# Roboteq_Board_V1_0.net
KiCad netlist of a schematic drawn in EAGLE
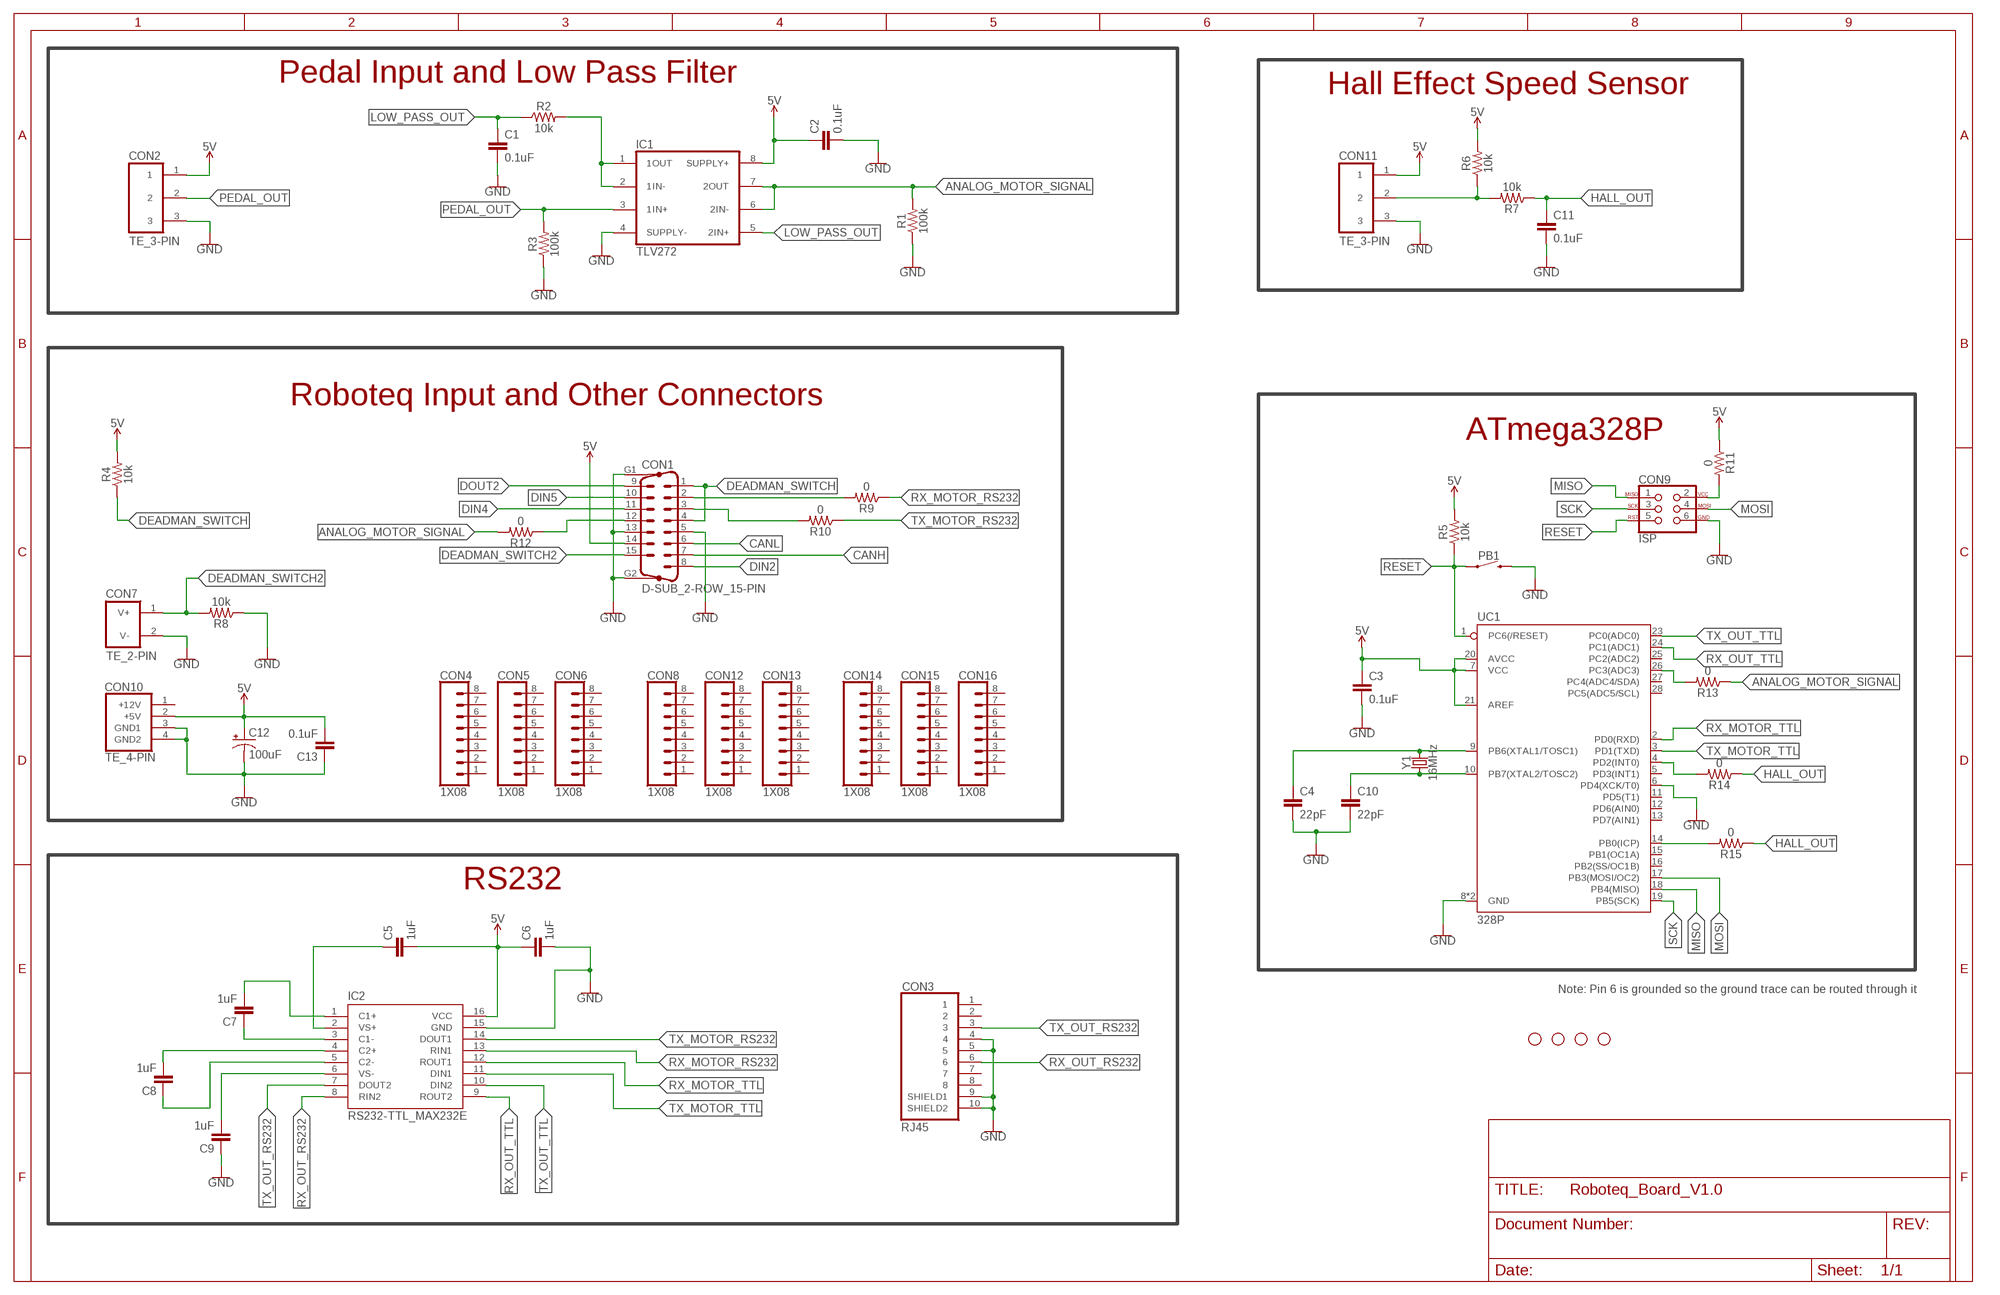
[diagram p0: schematic, sheet 1]

(export (version "E")
  (design (tool "Eeschema 10.0.6"))
  (components
    (comp (ref "C1")
      (value "0.1uF")
      (footprint "eagle-import:CAP-PTH-5MM")
      (libsource (lib "eagle-import") (part "CAPACITOR_CERAMIC_THROUGH-HOLE"))
    )
    (comp (ref "C2")
      (value "0.1uF")
      (footprint "eagle-import:CAP-PTH-5MM")
      (libsource (lib "eagle-import") (part "CAPACITOR_CERAMIC_THROUGH-HOLE"))
    )
    (comp (ref "C3")
      (value "0.1uF")
      (footprint "eagle-import:CAP-PTH-5MM")
      (libsource (lib "eagle-import") (part "CAPACITOR_CERAMIC_THROUGH-HOLE"))
    )
    (comp (ref "C4")
      (value "22pF")
      (footprint "eagle-import:CAP-PTH-5MM")
      (libsource (lib "eagle-import") (part "CAPACITOR_CERAMIC_THROUGH-HOLE"))
    )
    (comp (ref "C5")
      (value "1uF")
      (footprint "eagle-import:CAP-PTH-5MM")
      (libsource (lib "eagle-import") (part "CAPACITOR_CERAMIC_THROUGH-HOLE"))
    )
    (comp (ref "C6")
      (value "1uF")
      (footprint "eagle-import:CAP-PTH-5MM")
      (libsource (lib "eagle-import") (part "CAPACITOR_CERAMIC_THROUGH-HOLE"))
    )
    (comp (ref "C7")
      (value "1uF")
      (footprint "eagle-import:CAP-PTH-5MM")
      (libsource (lib "eagle-import") (part "CAPACITOR_CERAMIC_THROUGH-HOLE"))
    )
    (comp (ref "C8")
      (value "1uF")
      (footprint "eagle-import:CAP-PTH-5MM")
      (libsource (lib "eagle-import") (part "CAPACITOR_CERAMIC_THROUGH-HOLE"))
    )
    (comp (ref "C9")
      (value "1uF")
      (footprint "eagle-import:CAP-PTH-5MM")
      (libsource (lib "eagle-import") (part "CAPACITOR_CERAMIC_THROUGH-HOLE"))
    )
    (comp (ref "C10")
      (value "22pF")
      (footprint "eagle-import:CAP-PTH-5MM")
      (libsource (lib "eagle-import") (part "CAPACITOR_CERAMIC_THROUGH-HOLE"))
    )
    (comp (ref "C11")
      (value "0.1uF")
      (footprint "eagle-import:CAP-PTH-5MM")
      (libsource (lib "eagle-import") (part "CAPACITOR_CERAMIC_THROUGH-HOLE"))
    )
    (comp (ref "C12")
      (value "100uF")
      (footprint "eagle-import:CAPACITOR_100UF_50V")
      (libsource (lib "eagle-import") (part "CAPACITOR_ELECTROLYTIC_100UF"))
    )
    (comp (ref "C13")
      (value "0.1uF")
      (footprint "eagle-import:CAP-PTH-5MM")
      (libsource (lib "eagle-import") (part "CAPACITOR_CERAMIC_THROUGH-HOLE"))
    )
    (comp (ref "CON1")
      (value "D-SUB_2-ROW_15-PIN")
      (footprint "eagle-import:D-SUB_2-ROW_15-PIN")
      (libsource (lib "eagle-import") (part "D-SUB_2-ROW_15-PIN"))
    )
    (comp (ref "CON2")
      (value "TE_3-PIN")
      (footprint "eagle-import:TE_3-PIN")
      (libsource (lib "eagle-import") (part "TE_3-PIN"))
    )
    (comp (ref "CON3")
      (value "RJ45")
      (footprint "eagle-import:RJ45")
      (libsource (lib "eagle-import") (part "RJ45"))
    )
    (comp (ref "CON4")
      (value "1X08")
      (footprint "eagle-import:1X08")
      (libsource (lib "eagle-import") (part "1X08"))
    )
    (comp (ref "CON5")
      (value "1X08")
      (footprint "eagle-import:1X08")
      (libsource (lib "eagle-import") (part "1X08"))
    )
    (comp (ref "CON6")
      (value "1X08")
      (footprint "eagle-import:1X08")
      (libsource (lib "eagle-import") (part "1X08"))
    )
    (comp (ref "CON7")
      (value "TE_2-PIN")
      (footprint "eagle-import:TE_2-PIN")
      (libsource (lib "eagle-import") (part "TE_2-PIN"))
    )
    (comp (ref "CON8")
      (value "1X08")
      (footprint "eagle-import:1X08")
      (libsource (lib "eagle-import") (part "1X08"))
    )
    (comp (ref "CON9")
      (value "ISP")
      (footprint "eagle-import:ISP_CONNECTOR")
      (libsource (lib "eagle-import") (part "ISP"))
    )
    (comp (ref "CON10")
      (value "TE_4-PIN")
      (footprint "eagle-import:TE_4-PIN")
      (libsource (lib "eagle-import") (part "TE_4-PIN"))
    )
    (comp (ref "CON11")
      (value "TE_3-PIN")
      (footprint "eagle-import:TE_3-PIN")
      (libsource (lib "eagle-import") (part "TE_3-PIN"))
    )
    (comp (ref "CON12")
      (value "1X08")
      (footprint "eagle-import:1X08")
      (libsource (lib "eagle-import") (part "1X08"))
    )
    (comp (ref "CON13")
      (value "1X08")
      (footprint "eagle-import:1X08")
      (libsource (lib "eagle-import") (part "1X08"))
    )
    (comp (ref "CON14")
      (value "1X08")
      (footprint "eagle-import:1X08")
      (libsource (lib "eagle-import") (part "1X08"))
    )
    (comp (ref "CON15")
      (value "1X08")
      (footprint "eagle-import:1X08")
      (libsource (lib "eagle-import") (part "1X08"))
    )
    (comp (ref "CON16")
      (value "1X08")
      (footprint "eagle-import:1X08")
      (libsource (lib "eagle-import") (part "1X08"))
    )
    (comp (ref "H1")
      (value "STAND-OFF")
      (footprint "eagle-import:STAND-OFF")
      (libsource (lib "eagle-import") (part "STAND-OFF"))
    )
    (comp (ref "H2")
      (value "STAND-OFF")
      (footprint "eagle-import:STAND-OFF")
      (libsource (lib "eagle-import") (part "STAND-OFF"))
    )
    (comp (ref "H3")
      (value "STAND-OFF")
      (footprint "eagle-import:STAND-OFF")
      (libsource (lib "eagle-import") (part "STAND-OFF"))
    )
    (comp (ref "H4")
      (value "STAND-OFF")
      (footprint "eagle-import:STAND-OFF")
      (libsource (lib "eagle-import") (part "STAND-OFF"))
    )
    (comp (ref "IC1")
      (value "TLV272")
      (footprint "eagle-import:DIP08")
      (libsource (lib "eagle-import") (part "OP-AMP_DUAL"))
    )
    (comp (ref "IC2")
      (value "RS232-TTL_MAX232E")
      (footprint "eagle-import:DIP16")
      (libsource (lib "eagle-import") (part "RS232-TTL_MAX232E"))
    )
    (comp (ref "PB1")
      (value "PUSHBUTTON")
      (footprint "eagle-import:PUSHBUTTON")
      (libsource (lib "eagle-import") (part "PUSHBUTTON"))
    )
    (comp (ref "R1")
      (value "100k")
      (footprint "eagle-import:AXIAL-0.3")
      (libsource (lib "eagle-import") (part "RESISTOR_THROUGH-HOLE_1/4W"))
    )
    (comp (ref "R2")
      (value "10k")
      (footprint "eagle-import:AXIAL-0.3")
      (libsource (lib "eagle-import") (part "RESISTOR_THROUGH-HOLE_1/4W"))
    )
    (comp (ref "R3")
      (value "100k")
      (footprint "eagle-import:AXIAL-0.3")
      (libsource (lib "eagle-import") (part "RESISTOR_THROUGH-HOLE_1/4W"))
    )
    (comp (ref "R4")
      (value "10k")
      (footprint "eagle-import:AXIAL-0.3")
      (libsource (lib "eagle-import") (part "RESISTOR_THROUGH-HOLE_1/4W"))
    )
    (comp (ref "R5")
      (value "10k")
      (footprint "eagle-import:AXIAL-0.3")
      (libsource (lib "eagle-import") (part "RESISTOR_THROUGH-HOLE_1/4W"))
    )
    (comp (ref "R6")
      (value "10k")
      (footprint "eagle-import:AXIAL-0.3")
      (libsource (lib "eagle-import") (part "RESISTOR_THROUGH-HOLE_1/4W"))
    )
    (comp (ref "R7")
      (value "10k")
      (footprint "eagle-import:AXIAL-0.3")
      (libsource (lib "eagle-import") (part "RESISTOR_THROUGH-HOLE_1/4W"))
    )
    (comp (ref "R8")
      (value "10k")
      (footprint "eagle-import:AXIAL-0.3")
      (libsource (lib "eagle-import") (part "RESISTOR_THROUGH-HOLE_1/4W"))
    )
    (comp (ref "R9")
      (value "0")
      (footprint "eagle-import:AXIAL-0.3")
      (libsource (lib "eagle-import") (part "RESISTOR_THROUGH-HOLE_1/4W"))
    )
    (comp (ref "R10")
      (value "0")
      (footprint "eagle-import:AXIAL-0.3")
      (libsource (lib "eagle-import") (part "RESISTOR_THROUGH-HOLE_1/4W"))
    )
    (comp (ref "R11")
      (value "0")
      (footprint "eagle-import:AXIAL-0.3")
      (libsource (lib "eagle-import") (part "RESISTOR_THROUGH-HOLE_1/4W"))
    )
    (comp (ref "R12")
      (value "0")
      (footprint "eagle-import:AXIAL-0.3")
      (libsource (lib "eagle-import") (part "RESISTOR_THROUGH-HOLE_1/4W"))
    )
    (comp (ref "R13")
      (value "0")
      (footprint "eagle-import:AXIAL-0.3")
      (libsource (lib "eagle-import") (part "RESISTOR_THROUGH-HOLE_1/4W"))
    )
    (comp (ref "R14")
      (value "0")
      (footprint "eagle-import:AXIAL-0.3")
      (libsource (lib "eagle-import") (part "RESISTOR_THROUGH-HOLE_1/4W"))
    )
    (comp (ref "R15")
      (value "0")
      (footprint "eagle-import:AXIAL-0.3")
      (libsource (lib "eagle-import") (part "RESISTOR_THROUGH-HOLE_1/4W"))
    )
    (comp (ref "UC1")
      (value "328P")
      (footprint "eagle-import:DIP28")
      (libsource (lib "eagle-import") (part "ATMEGA328P_DIP28"))
    )
    (comp (ref "Y1")
      (value "16MHz")
      (footprint "eagle-import:HC49US")
      (libsource (lib "eagle-import") (part "CRYSTAL-16MHZPTH-HC49US"))
    )
  )
  (nets
    (net (code "1") (name "5V") (class "Default")
      (node (ref "C12") (pin "+") (pinfunction "+_+") (pintype "passive"))
      (node (ref "C13") (pin "2") (pinfunction "2_2") (pintype "passive"))
      (node (ref "C2") (pin "1") (pinfunction "1_1") (pintype "passive"))
      (node (ref "C3") (pin "1") (pinfunction "1_1") (pintype "passive"))
      (node (ref "C5") (pin "2") (pinfunction "2_2") (pintype "passive"))
      (node (ref "C6") (pin "1") (pinfunction "1_1") (pintype "passive"))
      (node (ref "CON1") (pin "14") (pinfunction "14_14") (pintype "passive"))
      (node (ref "CON10") (pin "2") (pinfunction "+5V_2") (pintype "passive"))
      (node (ref "CON11") (pin "1") (pinfunction "1_1") (pintype "passive"))
      (node (ref "CON2") (pin "1") (pinfunction "1_1") (pintype "passive"))
      (node (ref "IC1") (pin "8") (pinfunction "SUPPLY+_8") (pintype "bidirectional"))
      (node (ref "IC2") (pin "16") (pinfunction "VCC_16") (pintype "bidirectional"))
      (node (ref "R11") (pin "P$1") (pinfunction "1_P$1") (pintype "passive"))
      (node (ref "R4") (pin "P$2") (pinfunction "2_P$2") (pintype "passive"))
      (node (ref "R5") (pin "P$2") (pinfunction "2_P$2") (pintype "passive"))
      (node (ref "R6") (pin "P$2") (pinfunction "2_P$2") (pintype "passive"))
      (node (ref "UC1") (pin "20") (pinfunction "AVCC_20") (pintype "bidirectional"))
      (node (ref "UC1") (pin "21") (pinfunction "AREF_21") (pintype "bidirectional"))
      (node (ref "UC1") (pin "7") (pinfunction "VCC_7") (pintype "bidirectional"))
    )
    (net (code "2") (name "ANALOG_MOTOR_SIGNAL") (class "Default")
      (node (ref "IC1") (pin "6") (pinfunction "2IN-_6") (pintype "bidirectional"))
      (node (ref "IC1") (pin "7") (pinfunction "2OUT_7") (pintype "bidirectional"))
      (node (ref "R1") (pin "P$2") (pinfunction "2_P$2") (pintype "passive"))
      (node (ref "R12") (pin "P$2") (pinfunction "2_P$2") (pintype "passive"))
      (node (ref "R13") (pin "P$1") (pinfunction "1_P$1") (pintype "passive"))
    )
    (net (code "3") (name "CANH") (class "Default")
      (node (ref "CON1") (pin "7") (pinfunction "7_7") (pintype "passive"))
    )
    (net (code "4") (name "CANL") (class "Default")
      (node (ref "CON1") (pin "6") (pinfunction "6_6") (pintype "passive"))
    )
    (net (code "5") (name "DEADMAN_SWITCH") (class "Default")
      (node (ref "CON1") (pin "1") (pinfunction "1_1") (pintype "passive"))
      (node (ref "CON1") (pin "4") (pinfunction "4_4") (pintype "passive"))
      (node (ref "R4") (pin "P$1") (pinfunction "1_P$1") (pintype "passive"))
    )
    (net (code "6") (name "DEADMAN_SWITCH2") (class "Default")
      (node (ref "CON1") (pin "15") (pinfunction "15_15") (pintype "passive"))
      (node (ref "CON7") (pin "1") (pinfunction "V+_1") (pintype "passive"))
      (node (ref "R8") (pin "P$2") (pinfunction "2_P$2") (pintype "passive"))
    )
    (net (code "7") (name "DIN2") (class "Default")
      (node (ref "CON1") (pin "8") (pinfunction "8_8") (pintype "passive"))
    )
    (net (code "8") (name "DIN4") (class "Default")
      (node (ref "CON1") (pin "11") (pinfunction "11_11") (pintype "passive"))
    )
    (net (code "9") (name "DIN5") (class "Default")
      (node (ref "CON1") (pin "10") (pinfunction "10_10") (pintype "passive"))
    )
    (net (code "10") (name "DOUT2") (class "Default")
      (node (ref "CON1") (pin "9") (pinfunction "9_9") (pintype "passive"))
    )
    (net (code "11") (name "GND") (class "Default")
      (node (ref "C1") (pin "2") (pinfunction "2_2") (pintype "passive"))
      (node (ref "C10") (pin "2") (pinfunction "2_2") (pintype "passive"))
      (node (ref "C11") (pin "2") (pinfunction "2_2") (pintype "passive"))
      (node (ref "C12") (pin "-") (pinfunction "-_-") (pintype "passive"))
      (node (ref "C13") (pin "1") (pinfunction "1_1") (pintype "passive"))
      (node (ref "C2") (pin "2") (pinfunction "2_2") (pintype "passive"))
      (node (ref "C3") (pin "2") (pinfunction "2_2") (pintype "passive"))
      (node (ref "C4") (pin "2") (pinfunction "2_2") (pintype "passive"))
      (node (ref "C6") (pin "2") (pinfunction "2_2") (pintype "passive"))
      (node (ref "C9") (pin "1") (pinfunction "1_1") (pintype "passive"))
      (node (ref "CON1") (pin "13") (pinfunction "13_13") (pintype "passive"))
      (node (ref "CON1") (pin "5") (pinfunction "5_5") (pintype "passive"))
      (node (ref "CON1") (pin "G1") (pinfunction "GND1_G1") (pintype "passive"))
      (node (ref "CON1") (pin "G2") (pinfunction "GND2_G2") (pintype "passive"))
      (node (ref "CON10") (pin "3") (pinfunction "GND1_3") (pintype "passive"))
      (node (ref "CON10") (pin "4") (pinfunction "GND2_4") (pintype "passive"))
      (node (ref "CON11") (pin "3") (pinfunction "3_3") (pintype "passive"))
      (node (ref "CON2") (pin "3") (pinfunction "3_3") (pintype "passive"))
      (node (ref "CON3") (pin "10") (pinfunction "SHIELD2_10") (pintype "passive"))
      (node (ref "CON3") (pin "4") (pinfunction "4_4") (pintype "passive"))
      (node (ref "CON3") (pin "5") (pinfunction "5_5") (pintype "passive"))
      (node (ref "CON3") (pin "9") (pinfunction "SHIELD1_9") (pintype "passive"))
      (node (ref "CON7") (pin "2") (pinfunction "V-_2") (pintype "passive"))
      (node (ref "CON9") (pin "6") (pinfunction "6_6") (pintype "passive"))
      (node (ref "IC1") (pin "4") (pinfunction "SUPPLY-_4") (pintype "bidirectional"))
      (node (ref "IC2") (pin "15") (pinfunction "GND_15") (pintype "bidirectional"))
      (node (ref "PB1") (pin "3") (pinfunction "2_3") (pintype "passive"))
      (node (ref "PB1") (pin "4") (pinfunction "2_4") (pintype "passive"))
      (node (ref "R1") (pin "P$1") (pinfunction "1_P$1") (pintype "passive"))
      (node (ref "R3") (pin "P$1") (pinfunction "1_P$1") (pintype "passive"))
      (node (ref "R8") (pin "P$1") (pinfunction "1_P$1") (pintype "passive"))
      (node (ref "UC1") (pin "22") (pinfunction "GND_22") (pintype "bidirectional"))
      (node (ref "UC1") (pin "6") (pinfunction "PD4(XCK/T0)_6") (pintype "bidirectional"))
      (node (ref "UC1") (pin "8") (pinfunction "GND_8") (pintype "bidirectional"))
    )
    (net (code "12") (name "HALL_OUT") (class "Default")
      (node (ref "C11") (pin "1") (pinfunction "1_1") (pintype "passive"))
      (node (ref "R14") (pin "P$1") (pinfunction "1_P$1") (pintype "passive"))
      (node (ref "R15") (pin "P$1") (pinfunction "1_P$1") (pintype "passive"))
      (node (ref "R7") (pin "P$1") (pinfunction "1_P$1") (pintype "passive"))
    )
    (net (code "13") (name "LOW_PASS_OUT") (class "Default")
      (node (ref "C1") (pin "1") (pinfunction "1_1") (pintype "passive"))
      (node (ref "IC1") (pin "5") (pinfunction "2IN+_5") (pintype "bidirectional"))
      (node (ref "R2") (pin "P$1") (pinfunction "1_P$1") (pintype "passive"))
    )
    (net (code "14") (name "MISO") (class "Default")
      (node (ref "CON9") (pin "1") (pinfunction "1_1") (pintype "passive"))
      (node (ref "UC1") (pin "18") (pinfunction "PB4(MISO)_18") (pintype "bidirectional"))
    )
    (net (code "15") (name "MOSI") (class "Default")
      (node (ref "CON9") (pin "4") (pinfunction "4_4") (pintype "passive"))
      (node (ref "UC1") (pin "17") (pinfunction "PB3(MOSI/OC2)_17") (pintype "bidirectional"))
    )
    (net (code "16") (name "Net-(IC1-1IN-)") (class "Default")
      (node (ref "IC1") (pin "1") (pinfunction "1OUT_1") (pintype "bidirectional"))
      (node (ref "IC1") (pin "2") (pinfunction "1IN-_2") (pintype "bidirectional"))
      (node (ref "R2") (pin "P$2") (pinfunction "2_P$2") (pintype "passive"))
    )
    (net (code "17") (name "Net-(IC2-C1+)") (class "Default")
      (node (ref "C7") (pin "2") (pinfunction "2_2") (pintype "passive"))
      (node (ref "IC2") (pin "1") (pinfunction "C1+_1") (pintype "bidirectional"))
    )
    (net (code "18") (name "Net-(IC2-C1-)") (class "Default")
      (node (ref "C7") (pin "1") (pinfunction "1_1") (pintype "passive"))
      (node (ref "IC2") (pin "3") (pinfunction "C1-_3") (pintype "bidirectional"))
    )
    (net (code "19") (name "Net-(IC2-C2+)") (class "Default")
      (node (ref "C8") (pin "2") (pinfunction "2_2") (pintype "passive"))
      (node (ref "IC2") (pin "4") (pinfunction "C2+_4") (pintype "bidirectional"))
    )
    (net (code "20") (name "Net-(IC2-C2-)") (class "Default")
      (node (ref "C8") (pin "1") (pinfunction "1_1") (pintype "passive"))
      (node (ref "IC2") (pin "5") (pinfunction "C2-_5") (pintype "bidirectional"))
    )
    (net (code "21") (name "Net-(IC2-VS+)") (class "Default")
      (node (ref "C5") (pin "1") (pinfunction "1_1") (pintype "passive"))
      (node (ref "IC2") (pin "2") (pinfunction "VS+_2") (pintype "bidirectional"))
    )
    (net (code "22") (name "Net-(IC2-VS-)") (class "Default")
      (node (ref "C9") (pin "2") (pinfunction "2_2") (pintype "passive"))
      (node (ref "IC2") (pin "6") (pinfunction "VS-_6") (pintype "bidirectional"))
    )
    (net (code "23") (name "Net-(R6-1)") (class "Default")
      (node (ref "CON11") (pin "2") (pinfunction "2_2") (pintype "passive"))
      (node (ref "R6") (pin "P$1") (pinfunction "1_P$1") (pintype "passive"))
      (node (ref "R7") (pin "P$2") (pinfunction "2_P$2") (pintype "passive"))
    )
    (net (code "24") (name "Net-(R9-2)") (class "Default")
      (node (ref "CON1") (pin "2") (pinfunction "2_2") (pintype "passive"))
      (node (ref "R9") (pin "P$2") (pinfunction "2_P$2") (pintype "passive"))
    )
    (net (code "25") (name "Net-(R10-2)") (class "Default")
      (node (ref "CON1") (pin "3") (pinfunction "3_3") (pintype "passive"))
      (node (ref "R10") (pin "P$2") (pinfunction "2_P$2") (pintype "passive"))
    )
    (net (code "26") (name "Net-(R11-2)") (class "Default")
      (node (ref "CON9") (pin "2") (pinfunction "2_2") (pintype "passive"))
      (node (ref "R11") (pin "P$2") (pinfunction "2_P$2") (pintype "passive"))
    )
    (net (code "27") (name "Net-(R12-1)") (class "Default")
      (node (ref "CON1") (pin "12") (pinfunction "12_12") (pintype "passive"))
      (node (ref "R12") (pin "P$1") (pinfunction "1_P$1") (pintype "passive"))
    )
    (net (code "28") (name "Net-(R13-2)") (class "Default")
      (node (ref "R13") (pin "P$2") (pinfunction "2_P$2") (pintype "passive"))
      (node (ref "UC1") (pin "26") (pinfunction "PC3(ADC3)_26") (pintype "bidirectional"))
    )
    (net (code "29") (name "Net-(R14-2)") (class "Default")
      (node (ref "R14") (pin "P$2") (pinfunction "2_P$2") (pintype "passive"))
      (node (ref "UC1") (pin "4") (pinfunction "PD2(INT0)_4") (pintype "bidirectional"))
    )
    (net (code "30") (name "Net-(R15-2)") (class "Default")
      (node (ref "R15") (pin "P$2") (pinfunction "2_P$2") (pintype "passive"))
      (node (ref "UC1") (pin "14") (pinfunction "PB0(ICP)_14") (pintype "bidirectional"))
    )
    (net (code "31") (name "Net-(UC1-PB6(XTAL1{slash}TOSC1))") (class "Default")
      (node (ref "C4") (pin "1") (pinfunction "1_1") (pintype "passive"))
      (node (ref "UC1") (pin "9") (pinfunction "PB6(XTAL1/TOSC1)_9") (pintype "bidirectional"))
      (node (ref "Y1") (pin "2") (pinfunction "2_2") (pintype "passive"))
    )
    (net (code "32") (name "Net-(UC1-PB7(XTAL2{slash}TOSC2))") (class "Default")
      (node (ref "C10") (pin "1") (pinfunction "1_1") (pintype "passive"))
      (node (ref "UC1") (pin "10") (pinfunction "PB7(XTAL2/TOSC2)_10") (pintype "bidirectional"))
      (node (ref "Y1") (pin "1") (pinfunction "1_1") (pintype "passive"))
    )
    (net (code "33") (name "PEDAL_OUT") (class "Default")
      (node (ref "CON2") (pin "2") (pinfunction "2_2") (pintype "passive"))
      (node (ref "IC1") (pin "3") (pinfunction "1IN+_3") (pintype "bidirectional"))
      (node (ref "R3") (pin "P$2") (pinfunction "2_P$2") (pintype "passive"))
    )
    (net (code "34") (name "RESET") (class "Default")
      (node (ref "CON9") (pin "5") (pinfunction "5_5") (pintype "passive"))
      (node (ref "PB1") (pin "1") (pinfunction "1_1") (pintype "passive"))
      (node (ref "PB1") (pin "2") (pinfunction "1_2") (pintype "passive"))
      (node (ref "R5") (pin "P$1") (pinfunction "1_P$1") (pintype "passive"))
      (node (ref "UC1") (pin "1") (pinfunction "PC6(/RESET)_1") (pintype "bidirectional"))
    )
    (net (code "35") (name "RX_MOTOR_RS232") (class "Default")
      (node (ref "IC2") (pin "13") (pinfunction "RIN1_13") (pintype "bidirectional"))
      (node (ref "R9") (pin "P$1") (pinfunction "1_P$1") (pintype "passive"))
    )
    (net (code "36") (name "RX_MOTOR_TTL") (class "Default")
      (node (ref "IC2") (pin "12") (pinfunction "ROUT1_12") (pintype "bidirectional"))
      (node (ref "UC1") (pin "2") (pinfunction "PD0(RXD)_2") (pintype "bidirectional"))
    )
    (net (code "37") (name "RX_OUT_RS232") (class "Default")
      (node (ref "CON3") (pin "6") (pinfunction "6_6") (pintype "passive"))
      (node (ref "IC2") (pin "8") (pinfunction "RIN2_8") (pintype "bidirectional"))
    )
    (net (code "38") (name "RX_OUT_TTL") (class "Default")
      (node (ref "IC2") (pin "9") (pinfunction "ROUT2_9") (pintype "bidirectional"))
      (node (ref "UC1") (pin "24") (pinfunction "PC1(ADC1)_24") (pintype "bidirectional"))
    )
    (net (code "39") (name "SCK") (class "Default")
      (node (ref "CON9") (pin "3") (pinfunction "3_3") (pintype "passive"))
      (node (ref "UC1") (pin "19") (pinfunction "PB5(SCK)_19") (pintype "bidirectional"))
    )
    (net (code "40") (name "TX_MOTOR_RS232") (class "Default")
      (node (ref "IC2") (pin "14") (pinfunction "DOUT1_14") (pintype "bidirectional"))
      (node (ref "R10") (pin "P$1") (pinfunction "1_P$1") (pintype "passive"))
    )
    (net (code "41") (name "TX_MOTOR_TTL") (class "Default")
      (node (ref "IC2") (pin "11") (pinfunction "DIN1_11") (pintype "bidirectional"))
      (node (ref "UC1") (pin "3") (pinfunction "PD1(TXD)_3") (pintype "bidirectional"))
    )
    (net (code "42") (name "TX_OUT_RS232") (class "Default")
      (node (ref "CON3") (pin "3") (pinfunction "3_3") (pintype "passive"))
      (node (ref "IC2") (pin "7") (pinfunction "DOUT2_7") (pintype "bidirectional"))
    )
    (net (code "43") (name "TX_OUT_TTL") (class "Default")
      (node (ref "IC2") (pin "10") (pinfunction "DIN2_10") (pintype "bidirectional"))
      (node (ref "UC1") (pin "23") (pinfunction "PC0(ADC0)_23") (pintype "bidirectional"))
    )
    (net (code "44") (name "unconnected-(CON3-Pad1)") (class "Default")
      (node (ref "CON3") (pin "1") (pinfunction "1_1") (pintype "passive"))
    )
    (net (code "45") (name "unconnected-(CON3-Pad2)") (class "Default")
      (node (ref "CON3") (pin "2") (pinfunction "2_2") (pintype "passive"))
    )
    (net (code "46") (name "unconnected-(CON3-Pad7)") (class "Default")
      (node (ref "CON3") (pin "7") (pinfunction "7_7") (pintype "passive"))
    )
    (net (code "47") (name "unconnected-(CON3-Pad8)") (class "Default")
      (node (ref "CON3") (pin "8") (pinfunction "8_8") (pintype "passive"))
    )
    (net (code "48") (name "unconnected-(CON4-Pad1)") (class "Default")
      (node (ref "CON4") (pin "1") (pinfunction "1_1") (pintype "passive"))
    )
    (net (code "49") (name "unconnected-(CON4-Pad2)") (class "Default")
      (node (ref "CON4") (pin "2") (pinfunction "2_2") (pintype "passive"))
    )
    (net (code "50") (name "unconnected-(CON4-Pad3)") (class "Default")
      (node (ref "CON4") (pin "3") (pinfunction "3_3") (pintype "passive"))
    )
    (net (code "51") (name "unconnected-(CON4-Pad4)") (class "Default")
      (node (ref "CON4") (pin "4") (pinfunction "4_4") (pintype "passive"))
    )
    (net (code "52") (name "unconnected-(CON4-Pad5)") (class "Default")
      (node (ref "CON4") (pin "5") (pinfunction "5_5") (pintype "passive"))
    )
    (net (code "53") (name "unconnected-(CON4-Pad6)") (class "Default")
      (node (ref "CON4") (pin "6") (pinfunction "6_6") (pintype "passive"))
    )
    (net (code "54") (name "unconnected-(CON4-Pad7)") (class "Default")
      (node (ref "CON4") (pin "7") (pinfunction "7_7") (pintype "passive"))
    )
    (net (code "55") (name "unconnected-(CON4-Pad8)") (class "Default")
      (node (ref "CON4") (pin "8") (pinfunction "8_8") (pintype "passive"))
    )
    (net (code "56") (name "unconnected-(CON5-Pad1)") (class "Default")
      (node (ref "CON5") (pin "1") (pinfunction "1_1") (pintype "passive"))
    )
    (net (code "57") (name "unconnected-(CON5-Pad2)") (class "Default")
      (node (ref "CON5") (pin "2") (pinfunction "2_2") (pintype "passive"))
    )
    (net (code "58") (name "unconnected-(CON5-Pad3)") (class "Default")
      (node (ref "CON5") (pin "3") (pinfunction "3_3") (pintype "passive"))
    )
    (net (code "59") (name "unconnected-(CON5-Pad4)") (class "Default")
      (node (ref "CON5") (pin "4") (pinfunction "4_4") (pintype "passive"))
    )
    (net (code "60") (name "unconnected-(CON5-Pad5)") (class "Default")
      (node (ref "CON5") (pin "5") (pinfunction "5_5") (pintype "passive"))
    )
    (net (code "61") (name "unconnected-(CON5-Pad6)") (class "Default")
      (node (ref "CON5") (pin "6") (pinfunction "6_6") (pintype "passive"))
    )
    (net (code "62") (name "unconnected-(CON5-Pad7)") (class "Default")
      (node (ref "CON5") (pin "7") (pinfunction "7_7") (pintype "passive"))
    )
    (net (code "63") (name "unconnected-(CON5-Pad8)") (class "Default")
      (node (ref "CON5") (pin "8") (pinfunction "8_8") (pintype "passive"))
    )
    (net (code "64") (name "unconnected-(CON6-Pad1)") (class "Default")
      (node (ref "CON6") (pin "1") (pinfunction "1_1") (pintype "passive"))
    )
    (net (code "65") (name "unconnected-(CON6-Pad2)") (class "Default")
      (node (ref "CON6") (pin "2") (pinfunction "2_2") (pintype "passive"))
    )
    (net (code "66") (name "unconnected-(CON6-Pad3)") (class "Default")
      (node (ref "CON6") (pin "3") (pinfunction "3_3") (pintype "passive"))
    )
    (net (code "67") (name "unconnected-(CON6-Pad4)") (class "Default")
      (node (ref "CON6") (pin "4") (pinfunction "4_4") (pintype "passive"))
    )
    (net (code "68") (name "unconnected-(CON6-Pad5)") (class "Default")
      (node (ref "CON6") (pin "5") (pinfunction "5_5") (pintype "passive"))
    )
    (net (code "69") (name "unconnected-(CON6-Pad6)") (class "Default")
      (node (ref "CON6") (pin "6") (pinfunction "6_6") (pintype "passive"))
    )
    (net (code "70") (name "unconnected-(CON6-Pad7)") (class "Default")
      (node (ref "CON6") (pin "7") (pinfunction "7_7") (pintype "passive"))
    )
    (net (code "71") (name "unconnected-(CON6-Pad8)") (class "Default")
      (node (ref "CON6") (pin "8") (pinfunction "8_8") (pintype "passive"))
    )
    (net (code "72") (name "unconnected-(CON8-Pad1)") (class "Default")
      (node (ref "CON8") (pin "1") (pinfunction "1_1") (pintype "passive"))
    )
    (net (code "73") (name "unconnected-(CON8-Pad2)") (class "Default")
      (node (ref "CON8") (pin "2") (pinfunction "2_2") (pintype "passive"))
    )
    (net (code "74") (name "unconnected-(CON8-Pad3)") (class "Default")
      (node (ref "CON8") (pin "3") (pinfunction "3_3") (pintype "passive"))
    )
    (net (code "75") (name "unconnected-(CON8-Pad4)") (class "Default")
      (node (ref "CON8") (pin "4") (pinfunction "4_4") (pintype "passive"))
    )
    (net (code "76") (name "unconnected-(CON8-Pad5)") (class "Default")
      (node (ref "CON8") (pin "5") (pinfunction "5_5") (pintype "passive"))
    )
    (net (code "77") (name "unconnected-(CON8-Pad6)") (class "Default")
      (node (ref "CON8") (pin "6") (pinfunction "6_6") (pintype "passive"))
    )
    (net (code "78") (name "unconnected-(CON8-Pad7)") (class "Default")
      (node (ref "CON8") (pin "7") (pinfunction "7_7") (pintype "passive"))
    )
    (net (code "79") (name "unconnected-(CON8-Pad8)") (class "Default")
      (node (ref "CON8") (pin "8") (pinfunction "8_8") (pintype "passive"))
    )
    (net (code "80") (name "unconnected-(CON10-+12V-Pad1)") (class "Default")
      (node (ref "CON10") (pin "1") (pinfunction "+12V_1") (pintype "passive"))
    )
    (net (code "81") (name "unconnected-(CON12-Pad1)") (class "Default")
      (node (ref "CON12") (pin "1") (pinfunction "1_1") (pintype "passive"))
    )
    (net (code "82") (name "unconnected-(CON12-Pad2)") (class "Default")
      (node (ref "CON12") (pin "2") (pinfunction "2_2") (pintype "passive"))
    )
    (net (code "83") (name "unconnected-(CON12-Pad3)") (class "Default")
      (node (ref "CON12") (pin "3") (pinfunction "3_3") (pintype "passive"))
    )
    (net (code "84") (name "unconnected-(CON12-Pad4)") (class "Default")
      (node (ref "CON12") (pin "4") (pinfunction "4_4") (pintype "passive"))
    )
    (net (code "85") (name "unconnected-(CON12-Pad5)") (class "Default")
      (node (ref "CON12") (pin "5") (pinfunction "5_5") (pintype "passive"))
    )
    (net (code "86") (name "unconnected-(CON12-Pad6)") (class "Default")
      (node (ref "CON12") (pin "6") (pinfunction "6_6") (pintype "passive"))
    )
    (net (code "87") (name "unconnected-(CON12-Pad7)") (class "Default")
      (node (ref "CON12") (pin "7") (pinfunction "7_7") (pintype "passive"))
    )
    (net (code "88") (name "unconnected-(CON12-Pad8)") (class "Default")
      (node (ref "CON12") (pin "8") (pinfunction "8_8") (pintype "passive"))
    )
    (net (code "89") (name "unconnected-(CON13-Pad1)") (class "Default")
      (node (ref "CON13") (pin "1") (pinfunction "1_1") (pintype "passive"))
    )
    (net (code "90") (name "unconnected-(CON13-Pad2)") (class "Default")
      (node (ref "CON13") (pin "2") (pinfunction "2_2") (pintype "passive"))
    )
    (net (code "91") (name "unconnected-(CON13-Pad3)") (class "Default")
      (node (ref "CON13") (pin "3") (pinfunction "3_3") (pintype "passive"))
    )
    (net (code "92") (name "unconnected-(CON13-Pad4)") (class "Default")
      (node (ref "CON13") (pin "4") (pinfunction "4_4") (pintype "passive"))
    )
    (net (code "93") (name "unconnected-(CON13-Pad5)") (class "Default")
      (node (ref "CON13") (pin "5") (pinfunction "5_5") (pintype "passive"))
    )
    (net (code "94") (name "unconnected-(CON13-Pad6)") (class "Default")
      (node (ref "CON13") (pin "6") (pinfunction "6_6") (pintype "passive"))
    )
    (net (code "95") (name "unconnected-(CON13-Pad7)") (class "Default")
      (node (ref "CON13") (pin "7") (pinfunction "7_7") (pintype "passive"))
    )
    (net (code "96") (name "unconnected-(CON13-Pad8)") (class "Default")
      (node (ref "CON13") (pin "8") (pinfunction "8_8") (pintype "passive"))
    )
    (net (code "97") (name "unconnected-(CON14-Pad1)") (class "Default")
      (node (ref "CON14") (pin "1") (pinfunction "1_1") (pintype "passive"))
    )
    (net (code "98") (name "unconnected-(CON14-Pad2)") (class "Default")
      (node (ref "CON14") (pin "2") (pinfunction "2_2") (pintype "passive"))
    )
    (net (code "99") (name "unconnected-(CON14-Pad3)") (class "Default")
      (node (ref "CON14") (pin "3") (pinfunction "3_3") (pintype "passive"))
    )
    (net (code "100") (name "unconnected-(CON14-Pad4)") (class "Default")
      (node (ref "CON14") (pin "4") (pinfunction "4_4") (pintype "passive"))
    )
    (net (code "101") (name "unconnected-(CON14-Pad5)") (class "Default")
      (node (ref "CON14") (pin "5") (pinfunction "5_5") (pintype "passive"))
    )
    (net (code "102") (name "unconnected-(CON14-Pad6)") (class "Default")
      (node (ref "CON14") (pin "6") (pinfunction "6_6") (pintype "passive"))
    )
    (net (code "103") (name "unconnected-(CON14-Pad7)") (class "Default")
      (node (ref "CON14") (pin "7") (pinfunction "7_7") (pintype "passive"))
    )
    (net (code "104") (name "unconnected-(CON14-Pad8)") (class "Default")
      (node (ref "CON14") (pin "8") (pinfunction "8_8") (pintype "passive"))
    )
    (net (code "105") (name "unconnected-(CON15-Pad1)") (class "Default")
      (node (ref "CON15") (pin "1") (pinfunction "1_1") (pintype "passive"))
    )
    (net (code "106") (name "unconnected-(CON15-Pad2)") (class "Default")
      (node (ref "CON15") (pin "2") (pinfunction "2_2") (pintype "passive"))
    )
    (net (code "107") (name "unconnected-(CON15-Pad3)") (class "Default")
      (node (ref "CON15") (pin "3") (pinfunction "3_3") (pintype "passive"))
    )
    (net (code "108") (name "unconnected-(CON15-Pad4)") (class "Default")
      (node (ref "CON15") (pin "4") (pinfunction "4_4") (pintype "passive"))
    )
    (net (code "109") (name "unconnected-(CON15-Pad5)") (class "Default")
      (node (ref "CON15") (pin "5") (pinfunction "5_5") (pintype "passive"))
    )
    (net (code "110") (name "unconnected-(CON15-Pad6)") (class "Default")
      (node (ref "CON15") (pin "6") (pinfunction "6_6") (pintype "passive"))
    )
    (net (code "111") (name "unconnected-(CON15-Pad7)") (class "Default")
      (node (ref "CON15") (pin "7") (pinfunction "7_7") (pintype "passive"))
    )
    (net (code "112") (name "unconnected-(CON15-Pad8)") (class "Default")
      (node (ref "CON15") (pin "8") (pinfunction "8_8") (pintype "passive"))
    )
    (net (code "113") (name "unconnected-(CON16-Pad1)") (class "Default")
      (node (ref "CON16") (pin "1") (pinfunction "1_1") (pintype "passive"))
    )
    (net (code "114") (name "unconnected-(CON16-Pad2)") (class "Default")
      (node (ref "CON16") (pin "2") (pinfunction "2_2") (pintype "passive"))
    )
    (net (code "115") (name "unconnected-(CON16-Pad3)") (class "Default")
      (node (ref "CON16") (pin "3") (pinfunction "3_3") (pintype "passive"))
    )
    (net (code "116") (name "unconnected-(CON16-Pad4)") (class "Default")
      (node (ref "CON16") (pin "4") (pinfunction "4_4") (pintype "passive"))
    )
    (net (code "117") (name "unconnected-(CON16-Pad5)") (class "Default")
      (node (ref "CON16") (pin "5") (pinfunction "5_5") (pintype "passive"))
    )
    (net (code "118") (name "unconnected-(CON16-Pad6)") (class "Default")
      (node (ref "CON16") (pin "6") (pinfunction "6_6") (pintype "passive"))
    )
    (net (code "119") (name "unconnected-(CON16-Pad7)") (class "Default")
      (node (ref "CON16") (pin "7") (pinfunction "7_7") (pintype "passive"))
    )
    (net (code "120") (name "unconnected-(CON16-Pad8)") (class "Default")
      (node (ref "CON16") (pin "8") (pinfunction "8_8") (pintype "passive"))
    )
    (net (code "121") (name "unconnected-(UC1-PB1(OC1A)-Pad15)") (class "Default")
      (node (ref "UC1") (pin "15") (pinfunction "PB1(OC1A)_15") (pintype "bidirectional"))
    )
    (net (code "122") (name "unconnected-(UC1-PB2(SS{slash}OC1B)-Pad16)") (class "Default")
      (node (ref "UC1") (pin "16") (pinfunction "PB2(SS/OC1B)_16") (pintype "bidirectional"))
    )
    (net (code "123") (name "unconnected-(UC1-PC2(ADC2)-Pad25)") (class "Default")
      (node (ref "UC1") (pin "25") (pinfunction "PC2(ADC2)_25") (pintype "bidirectional"))
    )
    (net (code "124") (name "unconnected-(UC1-PC4(ADC4{slash}SDA)-Pad27)") (class "Default")
      (node (ref "UC1") (pin "27") (pinfunction "PC4(ADC4/SDA)_27") (pintype "bidirectional"))
    )
    (net (code "125") (name "unconnected-(UC1-PC5(ADC5{slash}SCL)-Pad28)") (class "Default")
      (node (ref "UC1") (pin "28") (pinfunction "PC5(ADC5/SCL)_28") (pintype "bidirectional"))
    )
    (net (code "126") (name "unconnected-(UC1-PD3(INT1)-Pad5)") (class "Default")
      (node (ref "UC1") (pin "5") (pinfunction "PD3(INT1)_5") (pintype "bidirectional"))
    )
    (net (code "127") (name "unconnected-(UC1-PD5(T1)-Pad11)") (class "Default")
      (node (ref "UC1") (pin "11") (pinfunction "PD5(T1)_11") (pintype "bidirectional"))
    )
    (net (code "128") (name "unconnected-(UC1-PD6(AIN0)-Pad12)") (class "Default")
      (node (ref "UC1") (pin "12") (pinfunction "PD6(AIN0)_12") (pintype "bidirectional"))
    )
    (net (code "129") (name "unconnected-(UC1-PD7(AIN1)-Pad13)") (class "Default")
      (node (ref "UC1") (pin "13") (pinfunction "PD7(AIN1)_13") (pintype "bidirectional"))
    )
  )
)
